# powerboard.net
KiCad netlist of a schematic drawn in EAGLE
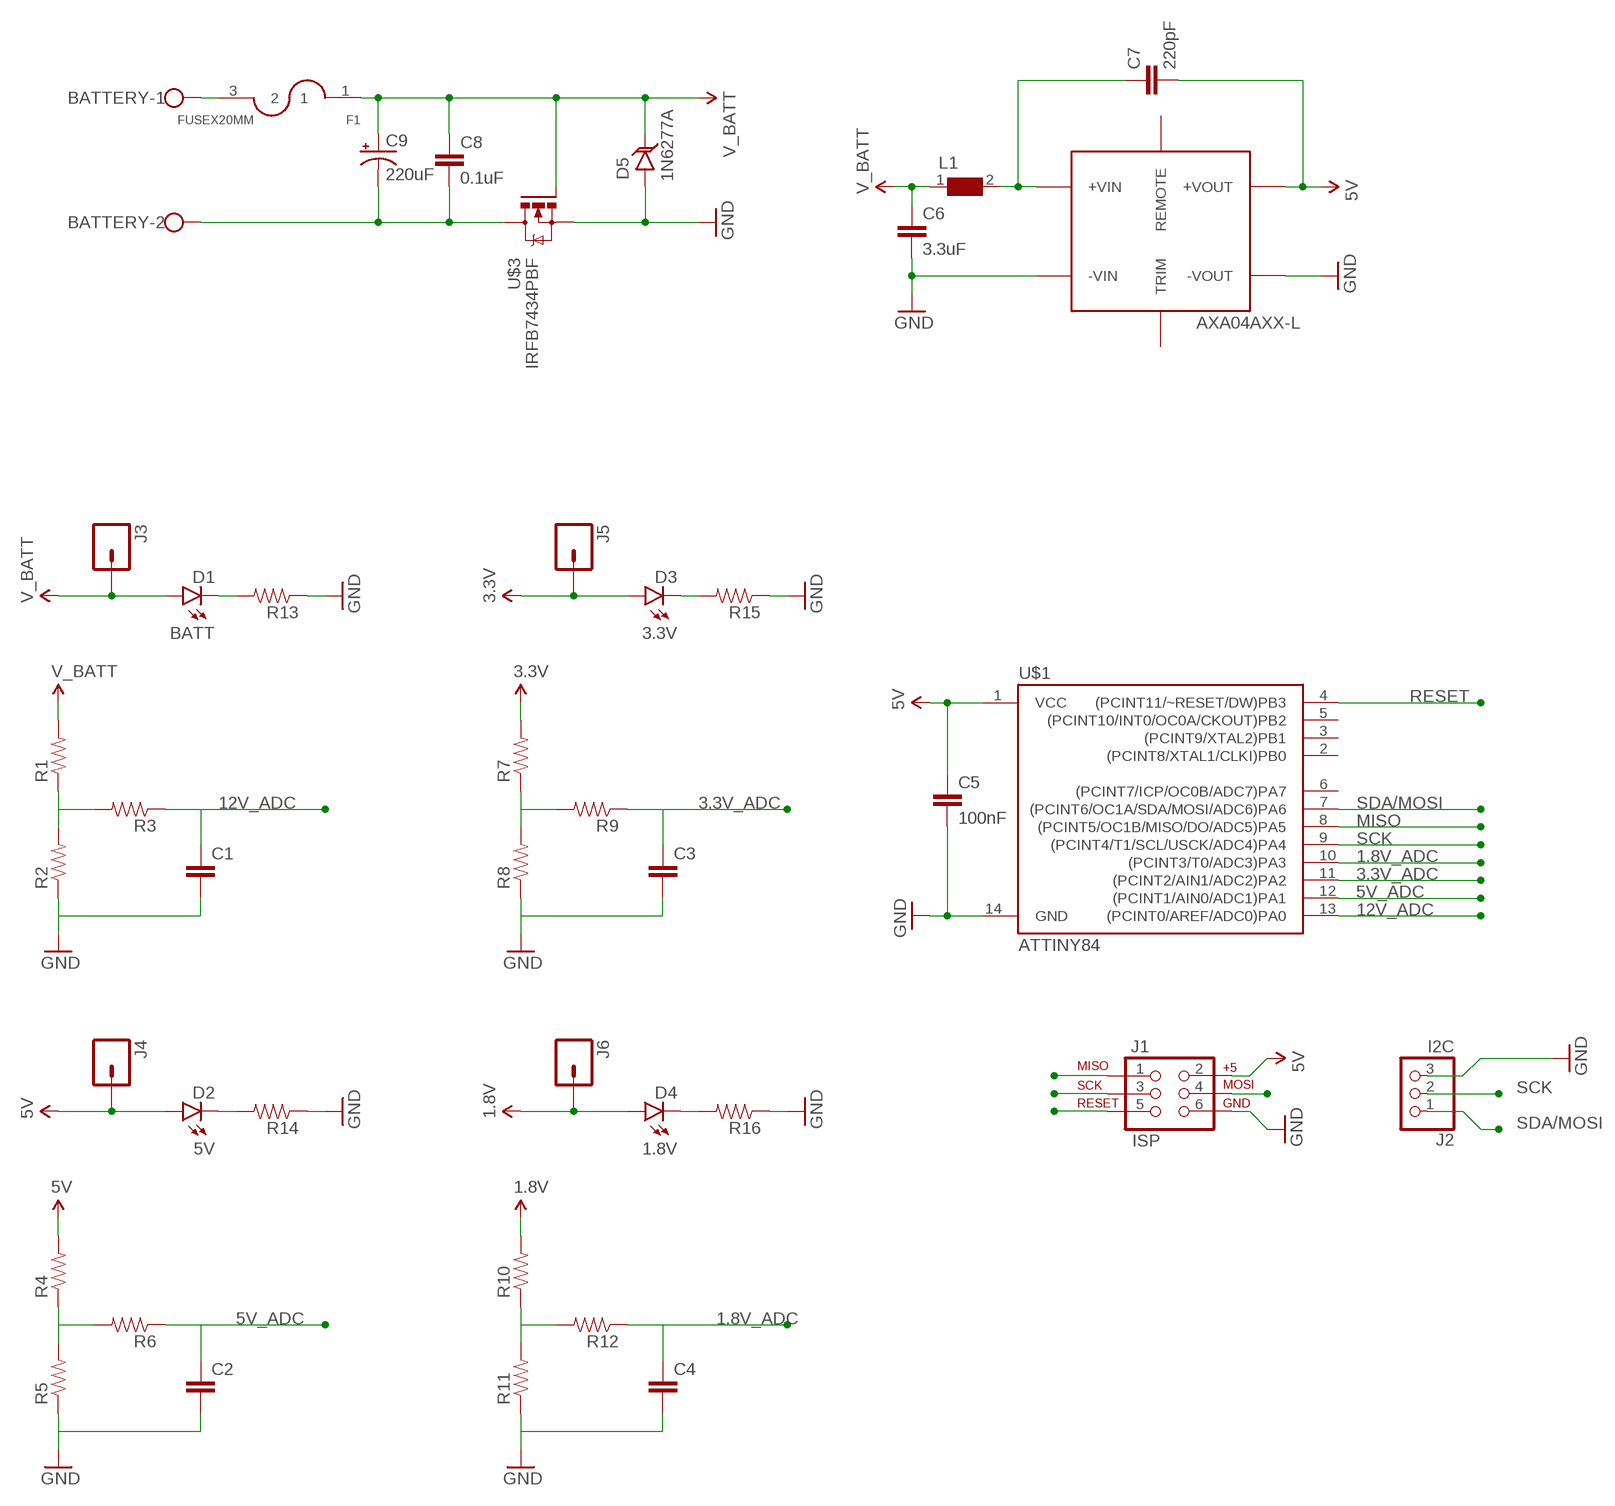
[diagram p0: schematic, sheet 1]

(export (version "E")
  (design (tool "Eeschema 10.0.6"))
  (components
    (comp (ref "BATTERY")
      (value "W237-102")
      (footprint "eagle-import:W237-102")
      (fields (field (name "MPN") "237-102"))
      (libsource (lib "eagle-import") (part "W237-102"))
    )
    (comp (ref "C1")
      (value "CAP0603-CAP")
      (footprint "eagle-import:0603-CAP")
      (libsource (lib "eagle-import") (part "CAP0603-CAP"))
    )
    (comp (ref "C2")
      (value "CAP0603-CAP")
      (footprint "eagle-import:0603-CAP")
      (libsource (lib "eagle-import") (part "CAP0603-CAP"))
    )
    (comp (ref "C3")
      (value "CAP0603-CAP")
      (footprint "eagle-import:0603-CAP")
      (libsource (lib "eagle-import") (part "CAP0603-CAP"))
    )
    (comp (ref "C4")
      (value "CAP0603-CAP")
      (footprint "eagle-import:0603-CAP")
      (libsource (lib "eagle-import") (part "CAP0603-CAP"))
    )
    (comp (ref "C5")
      (value "100nF")
      (footprint "eagle-import:0603-CAP")
      (libsource (lib "eagle-import") (part "CAP0603-CAP"))
    )
    (comp (ref "C6")
      (value "3.3uF")
      (footprint "eagle-import:1210")
      (libsource (lib "eagle-import") (part "CAP1210"))
    )
    (comp (ref "C7")
      (value "220pF")
      (footprint "eagle-import:C1808")
      (libsource (lib "eagle-import") (part "C-EUC1808"))
    )
    (comp (ref "C8")
      (value "0.1uF")
      (footprint "eagle-import:0603-CAP")
      (libsource (lib "eagle-import") (part "0.1UF-25V-5%(0603)"))
    )
    (comp (ref "C9")
      (value "220uF")
      (footprint "eagle-import:PANASONIC_G")
      (libsource (lib "eagle-import") (part "CPOL-USG"))
    )
    (comp (ref "D1")
      (value "BATT")
      (footprint "eagle-import:LED-0603")
      (libsource (lib "eagle-import") (part "LED0603"))
    )
    (comp (ref "D2")
      (value "5V")
      (footprint "eagle-import:LED-0603")
      (libsource (lib "eagle-import") (part "LED0603"))
    )
    (comp (ref "D3")
      (value "3.3V")
      (footprint "eagle-import:LED-0603")
      (libsource (lib "eagle-import") (part "LED0603"))
    )
    (comp (ref "D4")
      (value "1.8V")
      (footprint "eagle-import:LED-0603")
      (libsource (lib "eagle-import") (part "LED0603"))
    )
    (comp (ref "D5")
      (value "1N6277A")
      (footprint "eagle-import:1N6277A")
      (libsource (lib "eagle-import") (part "1N6277A"))
    )
    (comp (ref "F1")
      (value "FUSEX20MM")
      (footprint "eagle-import:FUSE_5MM")
      (libsource (lib "eagle-import") (part "FUSEX20MM"))
    )
    (comp (ref "J1")
      (value "ISP")
      (footprint "eagle-import:2X3")
      (libsource (lib "eagle-import") (part "AVR_SPI_PRG_6PTH"))
    )
    (comp (ref "J2")
      (value "I2C")
      (footprint "eagle-import:1X03_90")
      (libsource (lib "eagle-import") (part "PINHD-1X3/90"))
    )
    (comp (ref "J3")
      (value "M01NOSILK-KIT")
      (footprint "eagle-import:1X01NS-KIT")
      (libsource (lib "eagle-import") (part "M01NOSILK-KIT"))
    )
    (comp (ref "J4")
      (value "M01NOSILK-KIT")
      (footprint "eagle-import:1X01NS-KIT")
      (libsource (lib "eagle-import") (part "M01NOSILK-KIT"))
    )
    (comp (ref "J5")
      (value "M01NOSILK-KIT")
      (footprint "eagle-import:1X01NS-KIT")
      (libsource (lib "eagle-import") (part "M01NOSILK-KIT"))
    )
    (comp (ref "J6")
      (value "M01NOSILK-KIT")
      (footprint "eagle-import:1X01NS-KIT")
      (libsource (lib "eagle-import") (part "M01NOSILK-KIT"))
    )
    (comp (ref "L1")
      (value "WE-HCI-744314650_7030/7040/7050")
      (footprint "eagle-import:WE-HCI_7030_7040_7050")
      (fields (field (name "MPN") "744314650"))
      (libsource (lib "eagle-import") (part "WE-HCI_7030/7040/7050-744314650"))
    )
    (comp (ref "R1")
      (value "RESISTOR0603-RES")
      (footprint "eagle-import:0603-RES")
      (libsource (lib "eagle-import") (part "RESISTOR0603-RES"))
    )
    (comp (ref "R2")
      (value "RESISTOR0603-RES")
      (footprint "eagle-import:0603-RES")
      (libsource (lib "eagle-import") (part "RESISTOR0603-RES"))
    )
    (comp (ref "R3")
      (value "RESISTOR0603-RES")
      (footprint "eagle-import:0603-RES")
      (libsource (lib "eagle-import") (part "RESISTOR0603-RES"))
    )
    (comp (ref "R4")
      (value "RESISTOR0603-RES")
      (footprint "eagle-import:0603-RES")
      (libsource (lib "eagle-import") (part "RESISTOR0603-RES"))
    )
    (comp (ref "R5")
      (value "RESISTOR0603-RES")
      (footprint "eagle-import:0603-RES")
      (libsource (lib "eagle-import") (part "RESISTOR0603-RES"))
    )
    (comp (ref "R6")
      (value "RESISTOR0603-RES")
      (footprint "eagle-import:0603-RES")
      (libsource (lib "eagle-import") (part "RESISTOR0603-RES"))
    )
    (comp (ref "R7")
      (value "RESISTOR0603-RES")
      (footprint "eagle-import:0603-RES")
      (libsource (lib "eagle-import") (part "RESISTOR0603-RES"))
    )
    (comp (ref "R8")
      (value "RESISTOR0603-RES")
      (footprint "eagle-import:0603-RES")
      (libsource (lib "eagle-import") (part "RESISTOR0603-RES"))
    )
    (comp (ref "R9")
      (value "RESISTOR0603-RES")
      (footprint "eagle-import:0603-RES")
      (libsource (lib "eagle-import") (part "RESISTOR0603-RES"))
    )
    (comp (ref "R10")
      (value "RESISTOR0603-RES")
      (footprint "eagle-import:0603-RES")
      (libsource (lib "eagle-import") (part "RESISTOR0603-RES"))
    )
    (comp (ref "R11")
      (value "RESISTOR0603-RES")
      (footprint "eagle-import:0603-RES")
      (libsource (lib "eagle-import") (part "RESISTOR0603-RES"))
    )
    (comp (ref "R12")
      (value "RESISTOR0603-RES")
      (footprint "eagle-import:0603-RES")
      (libsource (lib "eagle-import") (part "RESISTOR0603-RES"))
    )
    (comp (ref "R13")
      (value "RESISTOR0603-RES")
      (footprint "eagle-import:0603-RES")
      (libsource (lib "eagle-import") (part "RESISTOR0603-RES"))
    )
    (comp (ref "R14")
      (value "RESISTOR0603-RES")
      (footprint "eagle-import:0603-RES")
      (libsource (lib "eagle-import") (part "RESISTOR0603-RES"))
    )
    (comp (ref "R15")
      (value "RESISTOR0603-RES")
      (footprint "eagle-import:0603-RES")
      (libsource (lib "eagle-import") (part "RESISTOR0603-RES"))
    )
    (comp (ref "R16")
      (value "RESISTOR0603-RES")
      (footprint "eagle-import:0603-RES")
      (libsource (lib "eagle-import") (part "RESISTOR0603-RES"))
    )
    (comp (ref "U$1")
      (value "ATTINY84")
      (footprint "eagle-import:SO14")
      (libsource (lib "eagle-import") (part "ATTINY84"))
    )
    (comp (ref "U$2")
      (value "AXA04AXX-L")
      (footprint "eagle-import:AXA04AXX-L")
      (libsource (lib "eagle-import") (part "AXA04AXX-L"))
    )
    (comp (ref "U$3")
      (value "IRFB7434PBF")
      (footprint "eagle-import:IRFB7434PBF")
      (libsource (lib "eagle-import") (part "IRFB7434PBF"))
    )
  )
  (nets
    (net (code "1") (name "/1.8V_ADC") (class "Default")
      (node (ref "C4") (pin "1") (pinfunction "1_1") (pintype "passive"))
      (node (ref "R12") (pin "1") (pinfunction "1_1") (pintype "passive"))
      (node (ref "U$1") (pin "10") (pinfunction "(PCINT3/T0/ADC3)PA3_10") (pintype "bidirectional"))
    )
    (net (code "2") (name "/3.3V_ADC") (class "Default")
      (node (ref "C3") (pin "1") (pinfunction "1_1") (pintype "passive"))
      (node (ref "R9") (pin "1") (pinfunction "1_1") (pintype "passive"))
      (node (ref "U$1") (pin "11") (pinfunction "(PCINT2/AIN1/ADC2)PA2_11") (pintype "bidirectional"))
    )
    (net (code "3") (name "/5V_ADC") (class "Default")
      (node (ref "C2") (pin "1") (pinfunction "1_1") (pintype "passive"))
      (node (ref "R6") (pin "1") (pinfunction "1_1") (pintype "passive"))
      (node (ref "U$1") (pin "12") (pinfunction "(PCINT1/AIN0/ADC1)PA1_12") (pintype "bidirectional"))
    )
    (net (code "4") (name "/12V_ADC") (class "Default")
      (node (ref "C1") (pin "1") (pinfunction "1_1") (pintype "passive"))
      (node (ref "R3") (pin "1") (pinfunction "1_1") (pintype "passive"))
      (node (ref "U$1") (pin "13") (pinfunction "(PCINT0/AREF/ADC0)PA0_13") (pintype "bidirectional"))
    )
    (net (code "5") (name "/MISO") (class "Default")
      (node (ref "J1") (pin "1") (pinfunction "1_1") (pintype "passive"))
      (node (ref "U$1") (pin "8") (pinfunction "(PCINT5/OC1B/MISO/DO/ADC5)PA5_8") (pintype "bidirectional"))
    )
    (net (code "6") (name "/RESET") (class "Default")
      (node (ref "J1") (pin "5") (pinfunction "5_5") (pintype "passive"))
      (node (ref "U$1") (pin "4") (pinfunction "(PCINT11/~{RESET/DW})PB3_4") (pintype "bidirectional"))
    )
    (net (code "7") (name "/SCK") (class "Default")
      (node (ref "J1") (pin "3") (pinfunction "3_3") (pintype "passive"))
      (node (ref "J2") (pin "2") (pinfunction "2_2") (pintype "passive"))
      (node (ref "U$1") (pin "9") (pinfunction "(PCINT4/T1/SCL/USCK/ADC4)PA4_9") (pintype "bidirectional"))
    )
    (net (code "8") (name "/SDA{slash}MOSI") (class "Default")
      (node (ref "J1") (pin "4") (pinfunction "4_4") (pintype "passive"))
      (node (ref "J2") (pin "1") (pinfunction "1_1") (pintype "passive"))
      (node (ref "U$1") (pin "7") (pinfunction "(PCINT6/OC1A/SDA/MOSI/ADC6)PA6_7") (pintype "bidirectional"))
    )
    (net (code "9") (name "1.8V") (class "Default")
      (node (ref "D4") (pin "A") (pinfunction "A_A") (pintype "passive"))
      (node (ref "J6") (pin "1") (pinfunction "1_1") (pintype "passive"))
      (node (ref "R10") (pin "2") (pinfunction "2_2") (pintype "passive"))
    )
    (net (code "10") (name "3.3V") (class "Default")
      (node (ref "D3") (pin "A") (pinfunction "A_A") (pintype "passive"))
      (node (ref "J5") (pin "1") (pinfunction "1_1") (pintype "passive"))
      (node (ref "R7") (pin "2") (pinfunction "2_2") (pintype "passive"))
    )
    (net (code "11") (name "5V") (class "Default")
      (node (ref "C5") (pin "1") (pinfunction "1_1") (pintype "passive"))
      (node (ref "C7") (pin "2") (pinfunction "2_2") (pintype "passive"))
      (node (ref "D2") (pin "A") (pinfunction "A_A") (pintype "passive"))
      (node (ref "J1") (pin "2") (pinfunction "2_2") (pintype "passive"))
      (node (ref "J4") (pin "1") (pinfunction "1_1") (pintype "passive"))
      (node (ref "R4") (pin "2") (pinfunction "2_2") (pintype "passive"))
      (node (ref "U$1") (pin "1") (pinfunction "VCC_1") (pintype "bidirectional"))
      (node (ref "U$2") (pin "+VOUT") (pinfunction "+VOUT_+VOUT") (pintype "bidirectional"))
    )
    (net (code "12") (name "GND") (class "Default")
      (node (ref "C1") (pin "2") (pinfunction "2_2") (pintype "passive"))
      (node (ref "C2") (pin "2") (pinfunction "2_2") (pintype "passive"))
      (node (ref "C3") (pin "2") (pinfunction "2_2") (pintype "passive"))
      (node (ref "C4") (pin "2") (pinfunction "2_2") (pintype "passive"))
      (node (ref "C5") (pin "2") (pinfunction "2_2") (pintype "passive"))
      (node (ref "C6") (pin "2") (pinfunction "2_2") (pintype "passive"))
      (node (ref "D5") (pin "A") (pinfunction "A_A") (pintype "passive"))
      (node (ref "J1") (pin "6") (pinfunction "6_6") (pintype "passive"))
      (node (ref "J2") (pin "3") (pinfunction "3_3") (pintype "passive"))
      (node (ref "R11") (pin "1") (pinfunction "1_1") (pintype "passive"))
      (node (ref "R13") (pin "1") (pinfunction "1_1") (pintype "passive"))
      (node (ref "R14") (pin "1") (pinfunction "1_1") (pintype "passive"))
      (node (ref "R15") (pin "1") (pinfunction "1_1") (pintype "passive"))
      (node (ref "R16") (pin "1") (pinfunction "1_1") (pintype "passive"))
      (node (ref "R2") (pin "1") (pinfunction "1_1") (pintype "passive"))
      (node (ref "R5") (pin "1") (pinfunction "1_1") (pintype "passive"))
      (node (ref "R8") (pin "1") (pinfunction "1_1") (pintype "passive"))
      (node (ref "U$1") (pin "14") (pinfunction "GND_14") (pintype "bidirectional"))
      (node (ref "U$2") (pin "-VIN") (pinfunction "-VIN_-VIN") (pintype "bidirectional"))
      (node (ref "U$2") (pin "-VOUT") (pinfunction "-VOUT_-VOUT") (pintype "bidirectional"))
      (node (ref "U$3") (pin "SOURCE") (pinfunction "S_SOURCE") (pintype "passive"))
    )
    (net (code "13") (name "Net-(BATTERYA-KL)") (class "Default")
      (node (ref "BATTERY") (pin "1") (pinfunction "KL_1") (pintype "passive"))
      (node (ref "F1") (pin "3") (pinfunction "2_3") (pintype "bidirectional"))
    )
    (net (code "14") (name "Net-(BATTERYB-KL)") (class "Default")
      (node (ref "BATTERY") (pin "2") (pinfunction "KL_2") (pintype "passive"))
      (node (ref "C8") (pin "2") (pinfunction "2_2") (pintype "passive"))
      (node (ref "C9") (pin "-") (pinfunction "-_-") (pintype "passive"))
      (node (ref "U$3") (pin "DRAIN") (pinfunction "D_DRAIN") (pintype "passive"))
    )
    (net (code "15") (name "Net-(C7-Pad1)") (class "Default")
      (node (ref "C7") (pin "1") (pinfunction "1_1") (pintype "passive"))
      (node (ref "L1") (pin "2") (pinfunction "2_2") (pintype "passive"))
      (node (ref "U$2") (pin "+VIN") (pinfunction "+VIN_+VIN") (pintype "bidirectional"))
    )
    (net (code "16") (name "Net-(D1-PadC)") (class "Default")
      (node (ref "D1") (pin "C") (pinfunction "C_C") (pintype "passive"))
      (node (ref "R13") (pin "2") (pinfunction "2_2") (pintype "passive"))
    )
    (net (code "17") (name "Net-(D2-PadC)") (class "Default")
      (node (ref "D2") (pin "C") (pinfunction "C_C") (pintype "passive"))
      (node (ref "R14") (pin "2") (pinfunction "2_2") (pintype "passive"))
    )
    (net (code "18") (name "Net-(D3-PadC)") (class "Default")
      (node (ref "D3") (pin "C") (pinfunction "C_C") (pintype "passive"))
      (node (ref "R15") (pin "2") (pinfunction "2_2") (pintype "passive"))
    )
    (net (code "19") (name "Net-(D4-PadC)") (class "Default")
      (node (ref "D4") (pin "C") (pinfunction "C_C") (pintype "passive"))
      (node (ref "R16") (pin "2") (pinfunction "2_2") (pintype "passive"))
    )
    (net (code "20") (name "Net-(R1-Pad1)") (class "Default")
      (node (ref "R1") (pin "1") (pinfunction "1_1") (pintype "passive"))
      (node (ref "R2") (pin "2") (pinfunction "2_2") (pintype "passive"))
      (node (ref "R3") (pin "2") (pinfunction "2_2") (pintype "passive"))
    )
    (net (code "21") (name "Net-(R4-Pad1)") (class "Default")
      (node (ref "R4") (pin "1") (pinfunction "1_1") (pintype "passive"))
      (node (ref "R5") (pin "2") (pinfunction "2_2") (pintype "passive"))
      (node (ref "R6") (pin "2") (pinfunction "2_2") (pintype "passive"))
    )
    (net (code "22") (name "Net-(R7-Pad1)") (class "Default")
      (node (ref "R7") (pin "1") (pinfunction "1_1") (pintype "passive"))
      (node (ref "R8") (pin "2") (pinfunction "2_2") (pintype "passive"))
      (node (ref "R9") (pin "2") (pinfunction "2_2") (pintype "passive"))
    )
    (net (code "23") (name "Net-(R10-Pad1)") (class "Default")
      (node (ref "R10") (pin "1") (pinfunction "1_1") (pintype "passive"))
      (node (ref "R11") (pin "2") (pinfunction "2_2") (pintype "passive"))
      (node (ref "R12") (pin "2") (pinfunction "2_2") (pintype "passive"))
    )
    (net (code "24") (name "V_BATT") (class "Default")
      (node (ref "C6") (pin "1") (pinfunction "1_1") (pintype "passive"))
      (node (ref "C8") (pin "1") (pinfunction "1_1") (pintype "passive"))
      (node (ref "C9") (pin "+") (pinfunction "+_+") (pintype "passive"))
      (node (ref "D1") (pin "A") (pinfunction "A_A") (pintype "passive"))
      (node (ref "D5") (pin "C") (pinfunction "C_C") (pintype "passive"))
      (node (ref "F1") (pin "1") (pinfunction "1_1") (pintype "bidirectional"))
      (node (ref "J3") (pin "1") (pinfunction "1_1") (pintype "passive"))
      (node (ref "L1") (pin "1") (pinfunction "1_1") (pintype "passive"))
      (node (ref "R1") (pin "2") (pinfunction "2_2") (pintype "passive"))
      (node (ref "U$3") (pin "GATE") (pinfunction "G_GATE") (pintype "passive"))
    )
    (net (code "25") (name "unconnected-(U$1-(PCINT7{slash}ICP{slash}OC0B{slash}ADC7)PA7-Pad6)") (class "Default")
      (node (ref "U$1") (pin "6") (pinfunction "(PCINT7/ICP/OC0B/ADC7)PA7_6") (pintype "bidirectional"))
    )
    (net (code "26") (name "unconnected-(U$1-(PCINT8{slash}XTAL1{slash}CLKI)PB0-Pad2)") (class "Default")
      (node (ref "U$1") (pin "2") (pinfunction "(PCINT8/XTAL1/CLKI)PB0_2") (pintype "bidirectional"))
    )
    (net (code "27") (name "unconnected-(U$1-(PCINT9{slash}XTAL2)PB1-Pad3)") (class "Default")
      (node (ref "U$1") (pin "3") (pinfunction "(PCINT9/XTAL2)PB1_3") (pintype "bidirectional"))
    )
    (net (code "28") (name "unconnected-(U$1-(PCINT10{slash}INT0{slash}OC0A{slash}CKOUT)PB2-Pad5)") (class "Default")
      (node (ref "U$1") (pin "5") (pinfunction "(PCINT10/INT0/OC0A/CKOUT)PB2_5") (pintype "bidirectional"))
    )
    (net (code "29") (name "unconnected-(U$2-PadREMOTE)") (class "Default")
      (node (ref "U$2") (pin "REMOTE") (pinfunction "REMOTE_REMOTE") (pintype "bidirectional"))
    )
    (net (code "30") (name "unconnected-(U$2-TRIM-PadTRIM{slash}COMMON)") (class "Default")
      (node (ref "U$2") (pin "TRIM/COMMON") (pinfunction "TRIM_TRIM/COMMON") (pintype "bidirectional"))
    )
  )
)
